# jeep_beacon.net
KiCad netlist of a schematic drawn in EAGLE
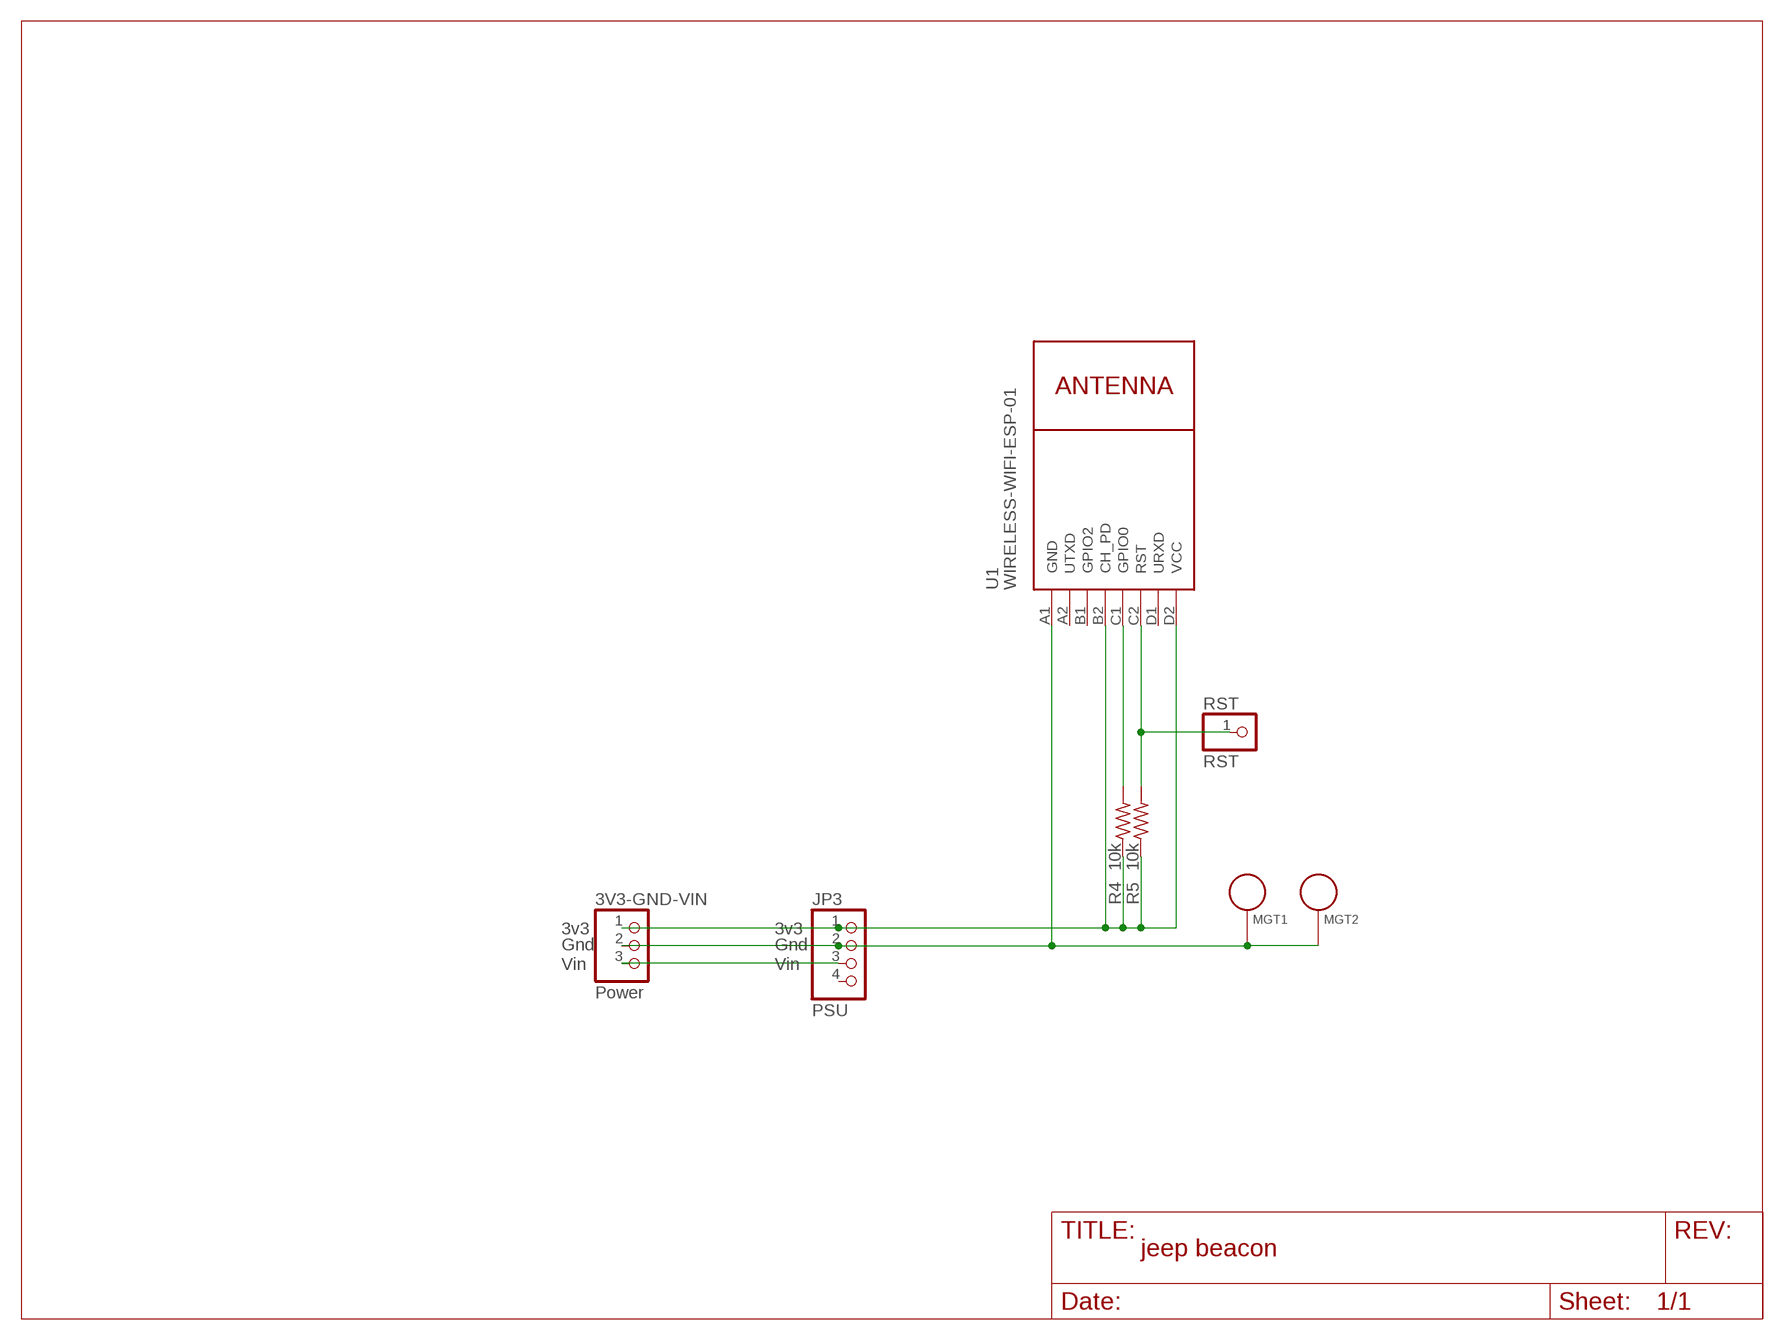
[diagram p0: schematic, sheet 1]

(export (version "E")
  (design (tool "Eeschema 10.0.6"))
  (components
    (comp (ref "3V3-GND-VIN")
      (value "Power")
      (footprint "eagle-import:1X03")
      (libsource (lib "eagle-import") (part "PINHD-1X3"))
    )
    (comp (ref "JP3")
      (value "PSU")
      (footprint "eagle-import:1X04")
      (libsource (lib "eagle-import") (part "PINHD-1X4"))
    )
    (comp (ref "MGT1")
      (value "BEAGLEBONEBLACK_MOUNTING_HOLE")
      (footprint "eagle-import:BEAGLEBONEBLACK_MOUNTING_HOLE")
      (libsource (lib "eagle-import") (part "BEAGLEBONEBLACK_MOUNTING_HOLE"))
    )
    (comp (ref "MGT2")
      (value "BEAGLEBONEBLACK_MOUNTING_HOLE")
      (footprint "eagle-import:BEAGLEBONEBLACK_MOUNTING_HOLE")
      (libsource (lib "eagle-import") (part "BEAGLEBONEBLACK_MOUNTING_HOLE"))
    )
    (comp (ref "R4")
      (value "10k")
      (footprint "eagle-import:0207_10")
      (libsource (lib "eagle-import") (part "R-US_0207/10"))
    )
    (comp (ref "R5")
      (value "10k")
      (footprint "eagle-import:0207_10")
      (libsource (lib "eagle-import") (part "R-US_0207/10"))
    )
    (comp (ref "RST")
      (value "RST")
      (footprint "eagle-import:1X01")
      (libsource (lib "eagle-import") (part "PINHD-1X1"))
    )
    (comp (ref "U1")
      (value "WIRELESS-WIFI-ESP-01")
      (footprint "eagle-import:WIRELESS-WIFI-ESP-01")
      (libsource (lib "eagle-import") (part "WIRELESS-WIFI-ESP-01"))
    )
  )
  (nets
    (net (code "1") (name "Net-(3V3-GND-VIN-Pad3)") (class "Default")
      (node (ref "3V3-GND-VIN") (pin "3") (pinfunction "3_3") (pintype "passive"))
      (node (ref "JP3") (pin "3") (pinfunction "3_3") (pintype "passive"))
    )
    (net (code "2") (name "Net-(U1-CH_PD)") (class "Default")
      (node (ref "3V3-GND-VIN") (pin "1") (pinfunction "1_1") (pintype "passive"))
      (node (ref "JP3") (pin "1") (pinfunction "1_1") (pintype "passive"))
      (node (ref "R4") (pin "1") (pinfunction "1_1") (pintype "passive"))
      (node (ref "R5") (pin "1") (pinfunction "1_1") (pintype "passive"))
      (node (ref "U1") (pin "B2") (pinfunction "CH_PD_B2") (pintype "bidirectional"))
      (node (ref "U1") (pin "D2") (pinfunction "VCC_D2") (pintype "power_in"))
    )
    (net (code "3") (name "Net-(U1-GND)") (class "Default")
      (node (ref "3V3-GND-VIN") (pin "2") (pinfunction "2_2") (pintype "passive"))
      (node (ref "JP3") (pin "2") (pinfunction "2_2") (pintype "passive"))
      (node (ref "MGT1") (pin "P$1") (pinfunction "P$1_P$1") (pintype "bidirectional"))
      (node (ref "MGT2") (pin "P$1") (pinfunction "P$1_P$1") (pintype "bidirectional"))
      (node (ref "U1") (pin "A1") (pinfunction "GND_A1") (pintype "power_in"))
    )
    (net (code "4") (name "Net-(U1-GPIO0)") (class "Default")
      (node (ref "R4") (pin "2") (pinfunction "2_2") (pintype "passive"))
      (node (ref "U1") (pin "C1") (pinfunction "GPIO0_C1") (pintype "bidirectional"))
    )
    (net (code "5") (name "Net-(U1-RST)") (class "Default")
      (node (ref "R5") (pin "2") (pinfunction "2_2") (pintype "passive"))
      (node (ref "RST") (pin "1") (pinfunction "1_1") (pintype "passive"))
      (node (ref "U1") (pin "C2") (pinfunction "RST_C2") (pintype "bidirectional"))
    )
    (net (code "6") (name "unconnected-(JP3-Pad4)") (class "Default")
      (node (ref "JP3") (pin "4") (pinfunction "4_4") (pintype "passive"))
    )
    (net (code "7") (name "unconnected-(U1-GPIO2-PadB1)") (class "Default")
      (node (ref "U1") (pin "B1") (pinfunction "GPIO2_B1") (pintype "bidirectional"))
    )
    (net (code "8") (name "unconnected-(U1-URXD-PadD1)") (class "Default")
      (node (ref "U1") (pin "D1") (pinfunction "URXD_D1") (pintype "bidirectional"))
    )
    (net (code "9") (name "unconnected-(U1-UTXD-PadA2)") (class "Default")
      (node (ref "U1") (pin "A2") (pinfunction "UTXD_A2") (pintype "bidirectional"))
    )
  )
)
